# pj13.net
KiCad netlist of a schematic drawn in EAGLE
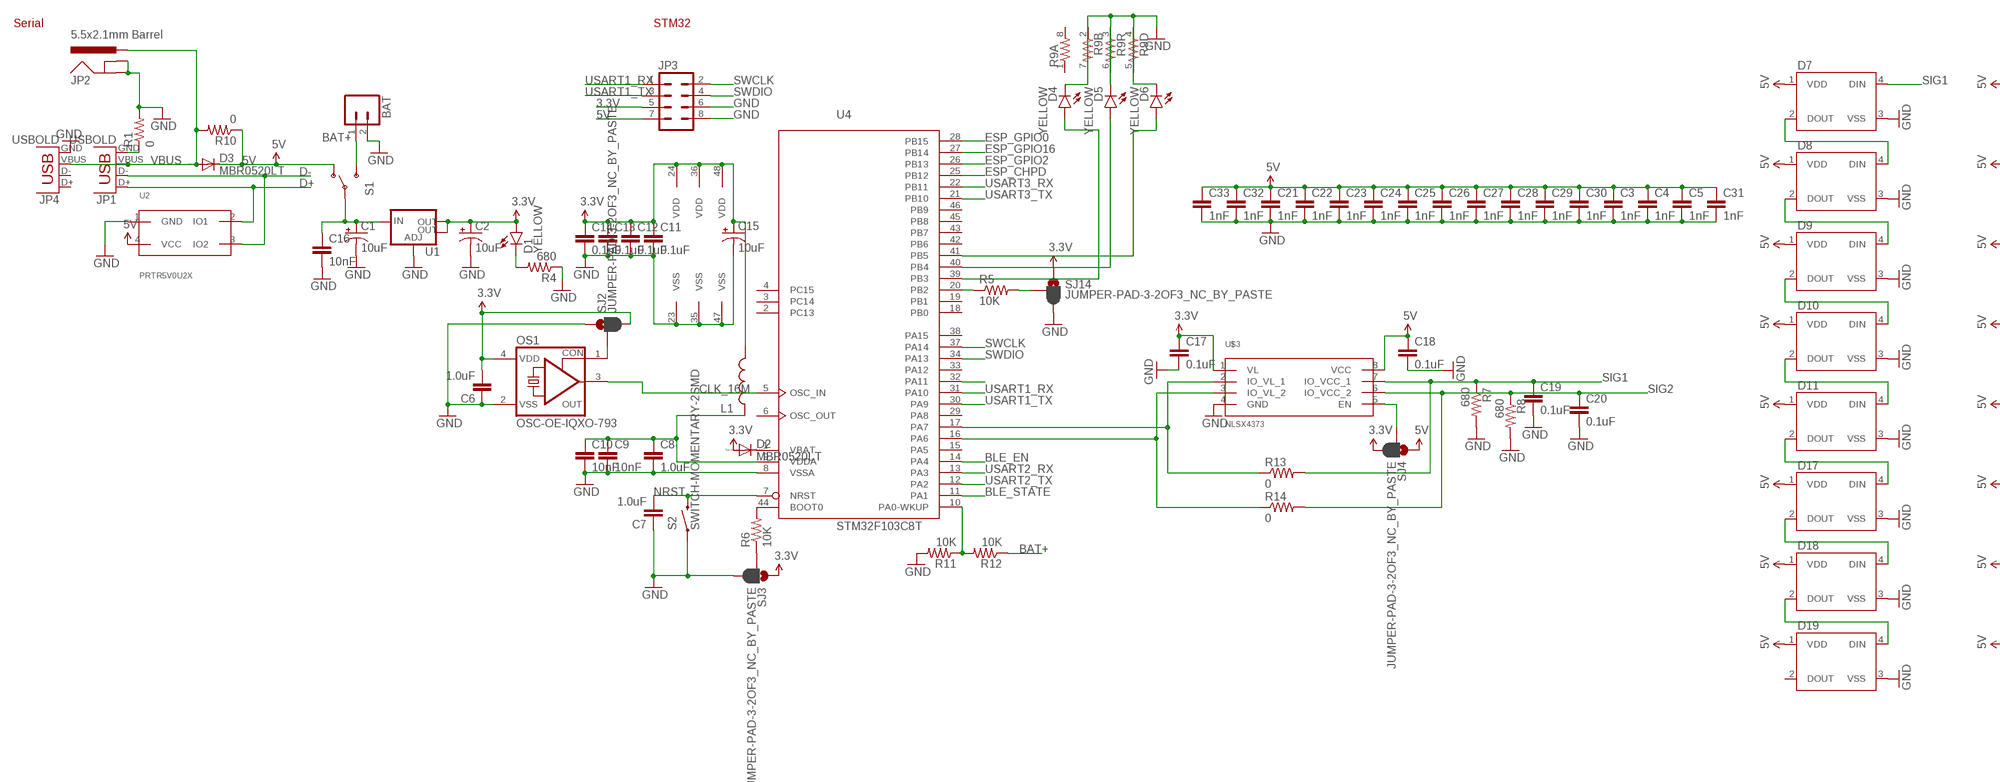
[diagram p0: schematic, sheet 1, part 1 of 2]
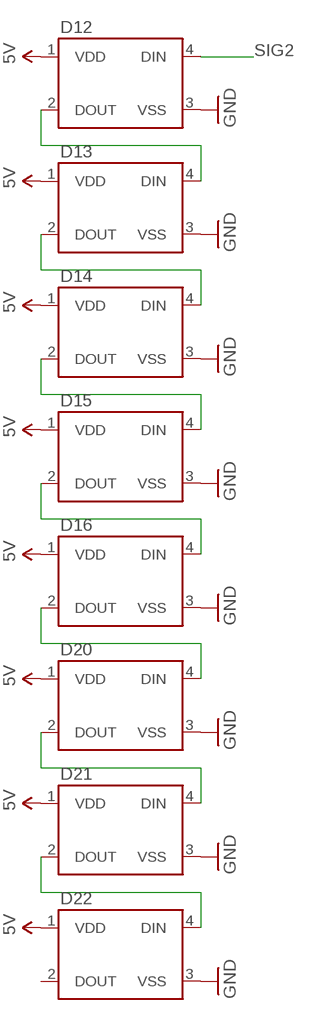
[diagram p1: schematic, sheet 1, part 2 of 2]

(export (version "E")
  (design (tool "Eeschema 10.0.6"))
  (components
    (comp (ref "BAT")
      (value "M02LOCK")
      (footprint "eagle-import:1X02_LOCK")
      (libsource (lib "eagle-import") (part "M02LOCK"))
    )
    (comp (ref "C1")
      (value "10uF")
      (footprint "eagle-import:EIA3216")
      (libsource (lib "eagle-import") (part "10UF-16V-10%(TANT)"))
    )
    (comp (ref "C2")
      (value "10uF")
      (footprint "eagle-import:EIA3216")
      (libsource (lib "eagle-import") (part "10UF-16V-10%(TANT)"))
    )
    (comp (ref "C3")
      (value "1nF")
      (footprint "eagle-import:0603-CAP")
      (libsource (lib "eagle-import") (part "0.1UF-25V-5%(0603)"))
    )
    (comp (ref "C4")
      (value "1nF")
      (footprint "eagle-import:0603-CAP")
      (libsource (lib "eagle-import") (part "0.1UF-25V-5%(0603)"))
    )
    (comp (ref "C5")
      (value "1nF")
      (footprint "eagle-import:0603-CAP")
      (libsource (lib "eagle-import") (part "0.1UF-25V-5%(0603)"))
    )
    (comp (ref "C6")
      (value "1.0uF")
      (footprint "eagle-import:0603-CAP")
      (libsource (lib "eagle-import") (part "1.0UF-16V-10%(0603)"))
    )
    (comp (ref "C7")
      (value "1.0uF")
      (footprint "eagle-import:0603-CAP")
      (libsource (lib "eagle-import") (part "1.0UF-16V-10%(0603)"))
    )
    (comp (ref "C8")
      (value "1.0uF")
      (footprint "eagle-import:0603-CAP")
      (libsource (lib "eagle-import") (part "1.0UF-16V-10%(0603)"))
    )
    (comp (ref "C9")
      (value "10nF")
      (footprint "eagle-import:0603-CAP")
      (libsource (lib "eagle-import") (part "10NF/10000PF-50V-10%(0603)"))
    )
    (comp (ref "C10")
      (value "10nF")
      (footprint "eagle-import:0603-CAP")
      (libsource (lib "eagle-import") (part "10NF/10000PF-50V-10%(0603)"))
    )
    (comp (ref "C11")
      (value "0.1uF")
      (footprint "eagle-import:0603-CAP")
      (libsource (lib "eagle-import") (part "0.1UF-25V-5%(0603)"))
    )
    (comp (ref "C12")
      (value "0.1uF")
      (footprint "eagle-import:0603-CAP")
      (libsource (lib "eagle-import") (part "0.1UF-25V-5%(0603)"))
    )
    (comp (ref "C13")
      (value "0.1uF")
      (footprint "eagle-import:0603-CAP")
      (libsource (lib "eagle-import") (part "0.1UF-25V-5%(0603)"))
    )
    (comp (ref "C14")
      (value "0.1uF")
      (footprint "eagle-import:0603-CAP")
      (libsource (lib "eagle-import") (part "0.1UF-25V-5%(0603)"))
    )
    (comp (ref "C15")
      (value "10uF")
      (footprint "eagle-import:EIA3216")
      (libsource (lib "eagle-import") (part "10UF-16V-10%(TANT)"))
    )
    (comp (ref "C16")
      (value "10nF")
      (footprint "eagle-import:0603-CAP")
      (libsource (lib "eagle-import") (part "10NF/10000PF-50V-10%(0603)"))
    )
    (comp (ref "C17")
      (value "0.1uF")
      (footprint "eagle-import:0603-CAP")
      (libsource (lib "eagle-import") (part "0.1UF-25V-5%(0603)"))
    )
    (comp (ref "C18")
      (value "0.1uF")
      (footprint "eagle-import:0603-CAP")
      (libsource (lib "eagle-import") (part "0.1UF-25V-5%(0603)"))
    )
    (comp (ref "C19")
      (value "0.1uF")
      (footprint "eagle-import:0603-CAP")
      (libsource (lib "eagle-import") (part "0.1UF-25V-5%(0603)"))
    )
    (comp (ref "C20")
      (value "0.1uF")
      (footprint "eagle-import:0603-CAP")
      (libsource (lib "eagle-import") (part "0.1UF-25V-5%(0603)"))
    )
    (comp (ref "C21")
      (value "1nF")
      (footprint "eagle-import:0603-CAP")
      (libsource (lib "eagle-import") (part "0.1UF-25V-5%(0603)"))
    )
    (comp (ref "C22")
      (value "1nF")
      (footprint "eagle-import:0603-CAP")
      (libsource (lib "eagle-import") (part "0.1UF-25V-5%(0603)"))
    )
    (comp (ref "C23")
      (value "1nF")
      (footprint "eagle-import:0603-CAP")
      (libsource (lib "eagle-import") (part "0.1UF-25V-5%(0603)"))
    )
    (comp (ref "C24")
      (value "1nF")
      (footprint "eagle-import:0603-CAP")
      (libsource (lib "eagle-import") (part "0.1UF-25V-5%(0603)"))
    )
    (comp (ref "C25")
      (value "1nF")
      (footprint "eagle-import:0603-CAP")
      (libsource (lib "eagle-import") (part "0.1UF-25V-5%(0603)"))
    )
    (comp (ref "C26")
      (value "1nF")
      (footprint "eagle-import:0603-CAP")
      (libsource (lib "eagle-import") (part "0.1UF-25V-5%(0603)"))
    )
    (comp (ref "C27")
      (value "1nF")
      (footprint "eagle-import:0603-CAP")
      (libsource (lib "eagle-import") (part "0.1UF-25V-5%(0603)"))
    )
    (comp (ref "C28")
      (value "1nF")
      (footprint "eagle-import:0603-CAP")
      (libsource (lib "eagle-import") (part "0.1UF-25V-5%(0603)"))
    )
    (comp (ref "C29")
      (value "1nF")
      (footprint "eagle-import:0603-CAP")
      (libsource (lib "eagle-import") (part "0.1UF-25V-5%(0603)"))
    )
    (comp (ref "C30")
      (value "1nF")
      (footprint "eagle-import:0603-CAP")
      (libsource (lib "eagle-import") (part "0.1UF-25V-5%(0603)"))
    )
    (comp (ref "C31")
      (value "1nF")
      (footprint "eagle-import:0603-CAP")
      (libsource (lib "eagle-import") (part "0.1UF-25V-5%(0603)"))
    )
    (comp (ref "C32")
      (value "1nF")
      (footprint "eagle-import:0603-CAP")
      (libsource (lib "eagle-import") (part "0.1UF-25V-5%(0603)"))
    )
    (comp (ref "C33")
      (value "1nF")
      (footprint "eagle-import:0603-CAP")
      (libsource (lib "eagle-import") (part "0.1UF-25V-5%(0603)"))
    )
    (comp (ref "D1")
      (value "YELLOW")
      (footprint "eagle-import:LED-1206")
      (libsource (lib "eagle-import") (part "LED-YELLOW1206"))
    )
    (comp (ref "D2")
      (value "MBR0520LT")
      (footprint "eagle-import:SOD123")
      (libsource (lib "eagle-import") (part "MBR0520LT"))
    )
    (comp (ref "D3")
      (value "MBR0520LT")
      (footprint "eagle-import:SOD123")
      (libsource (lib "eagle-import") (part "MBR0520LT"))
    )
    (comp (ref "D4")
      (value "YELLOW")
      (footprint "eagle-import:LED-1206")
      (libsource (lib "eagle-import") (part "LED-YELLOW1206"))
    )
    (comp (ref "D5")
      (value "YELLOW")
      (footprint "eagle-import:LED-1206")
      (libsource (lib "eagle-import") (part "LED-YELLOW1206"))
    )
    (comp (ref "D6")
      (value "YELLOW")
      (footprint "eagle-import:LED-1206")
      (libsource (lib "eagle-import") (part "LED-YELLOW1206"))
    )
    (comp (ref "D7")
      (value "WS2812B")
      (footprint "eagle-import:WS2812B")
      (libsource (lib "eagle-import") (part "WS2812B"))
    )
    (comp (ref "D8")
      (value "WS2812B")
      (footprint "eagle-import:WS2812B")
      (libsource (lib "eagle-import") (part "WS2812B"))
    )
    (comp (ref "D9")
      (value "WS2812B")
      (footprint "eagle-import:WS2812B")
      (libsource (lib "eagle-import") (part "WS2812B"))
    )
    (comp (ref "D10")
      (value "WS2812B")
      (footprint "eagle-import:WS2812B")
      (libsource (lib "eagle-import") (part "WS2812B"))
    )
    (comp (ref "D11")
      (value "WS2812B")
      (footprint "eagle-import:WS2812B")
      (libsource (lib "eagle-import") (part "WS2812B"))
    )
    (comp (ref "D12")
      (value "WS2812B")
      (footprint "eagle-import:WS2812B")
      (libsource (lib "eagle-import") (part "WS2812B"))
    )
    (comp (ref "D13")
      (value "WS2812B")
      (footprint "eagle-import:WS2812B")
      (libsource (lib "eagle-import") (part "WS2812B"))
    )
    (comp (ref "D14")
      (value "WS2812B")
      (footprint "eagle-import:WS2812B")
      (libsource (lib "eagle-import") (part "WS2812B"))
    )
    (comp (ref "D15")
      (value "WS2812B")
      (footprint "eagle-import:WS2812B")
      (libsource (lib "eagle-import") (part "WS2812B"))
    )
    (comp (ref "D16")
      (value "WS2812B")
      (footprint "eagle-import:WS2812B")
      (libsource (lib "eagle-import") (part "WS2812B"))
    )
    (comp (ref "D17")
      (value "WS2812B")
      (footprint "eagle-import:WS2812B")
      (libsource (lib "eagle-import") (part "WS2812B"))
    )
    (comp (ref "D18")
      (value "WS2812B")
      (footprint "eagle-import:WS2812B")
      (libsource (lib "eagle-import") (part "WS2812B"))
    )
    (comp (ref "D19")
      (value "WS2812B")
      (footprint "eagle-import:WS2812B")
      (libsource (lib "eagle-import") (part "WS2812B"))
    )
    (comp (ref "D20")
      (value "WS2812B")
      (footprint "eagle-import:WS2812B")
      (libsource (lib "eagle-import") (part "WS2812B"))
    )
    (comp (ref "D21")
      (value "WS2812B")
      (footprint "eagle-import:WS2812B")
      (libsource (lib "eagle-import") (part "WS2812B"))
    )
    (comp (ref "D22")
      (value "WS2812B")
      (footprint "eagle-import:WS2812B")
      (libsource (lib "eagle-import") (part "WS2812B"))
    )
    (comp (ref "JP1")
      (value "USBOLD")
      (footprint "eagle-import:USB-MINIB-OLD")
      (libsource (lib "eagle-import") (part "USBOLD"))
    )
    (comp (ref "JP2")
      (value "5.5x2.1mm Barrel")
      (footprint "eagle-import:POWER_JACK_SMD")
      (libsource (lib "eagle-import") (part "POWER_JACKSMD"))
    )
    (comp (ref "JP3")
      (value "M04X2SMD")
      (footprint "eagle-import:2X4_SMD")
      (libsource (lib "eagle-import") (part "M04X2SMD"))
    )
    (comp (ref "JP4")
      (value "USBOLD")
      (footprint "eagle-import:USB-MINIB-OLD")
      (libsource (lib "eagle-import") (part "USBOLD"))
    )
    (comp (ref "L1")
      (value "INDUCTOR0603")
      (footprint "eagle-import:0603")
      (libsource (lib "eagle-import") (part "INDUCTOR0603"))
    )
    (comp (ref "OS1")
      (value "OSC-OE-IQXO-793")
      (footprint "eagle-import:2.5X2-4-PAD")
      (libsource (lib "eagle-import") (part "OSC-OE-IQXO-793"))
    )
    (comp (ref "R1")
      (value "0")
      (footprint "eagle-import:0603")
      (libsource (lib "eagle-import") (part "0OHM-1/10W-5%(0603)"))
    )
    (comp (ref "R4")
      (value "680")
      (footprint "eagle-import:0603-RES")
      (libsource (lib "eagle-import") (part "680OHM1/10W5%(0603)"))
    )
    (comp (ref "R5")
      (value "10K")
      (footprint "eagle-import:0603-RES")
      (libsource (lib "eagle-import") (part "10KOHM-1/10W-1%(0603)0603"))
    )
    (comp (ref "R6")
      (value "10K")
      (footprint "eagle-import:0603-RES")
      (libsource (lib "eagle-import") (part "10KOHM-1/10W-1%(0603)0603"))
    )
    (comp (ref "R7")
      (value "680")
      (footprint "eagle-import:0603-RES")
      (libsource (lib "eagle-import") (part "680OHM1/10W5%(0603)"))
    )
    (comp (ref "R8")
      (value "680")
      (footprint "eagle-import:0603-RES")
      (libsource (lib "eagle-import") (part "680OHM1/10W5%(0603)"))
    )
    (comp (ref "R9")
      (value "RESISTOR-ARRAY0603-ARV")
      (footprint "eagle-import:0603-ARV")
      (libsource (lib "eagle-import") (part "RESISTOR-ARRAY0603-ARV"))
    )
    (comp (ref "R10")
      (value "0")
      (footprint "eagle-import:0603")
      (libsource (lib "eagle-import") (part "0OHM-1/10W-5%(0603)"))
    )
    (comp (ref "R11")
      (value "10K")
      (footprint "eagle-import:0603-RES")
      (libsource (lib "eagle-import") (part "10KOHM-1/10W-1%(0603)0603"))
    )
    (comp (ref "R12")
      (value "10K")
      (footprint "eagle-import:0603-RES")
      (libsource (lib "eagle-import") (part "10KOHM-1/10W-1%(0603)0603"))
    )
    (comp (ref "R13")
      (value "0")
      (footprint "eagle-import:0603-RES")
      (libsource (lib "eagle-import") (part "680OHM1/10W5%(0603)"))
    )
    (comp (ref "R14")
      (value "0")
      (footprint "eagle-import:0603-RES")
      (libsource (lib "eagle-import") (part "680OHM1/10W5%(0603)"))
    )
    (comp (ref "S1")
      (value "SWITCH-SPDTSMD")
      (footprint "eagle-import:AYZ0202")
      (libsource (lib "eagle-import") (part "SWITCH-SPDTSMD"))
    )
    (comp (ref "S2")
      (value "SWITCH-MOMENTARY-2SMD")
      (footprint "eagle-import:TACTILE-SWITCH-SMD")
      (libsource (lib "eagle-import") (part "SWITCH-MOMENTARY-2SMD"))
    )
    (comp (ref "SJ2")
      (value "JUMPER-PAD-3-2OF3_NC_BY_PASTE")
      (footprint "eagle-import:PAD-JUMPER-3-2OF3_NC_BY_PASTE_YES_SILK_FULL_BOX")
      (libsource (lib "eagle-import") (part "JUMPER-PAD-3-2OF3_NC_BY_PASTE"))
    )
    (comp (ref "SJ3")
      (value "JUMPER-PAD-3-2OF3_NC_BY_PASTE")
      (footprint "eagle-import:PAD-JUMPER-3-2OF3_NC_BY_PASTE_YES_SILK_FULL_BOX")
      (libsource (lib "eagle-import") (part "JUMPER-PAD-3-2OF3_NC_BY_PASTE"))
    )
    (comp (ref "SJ4")
      (value "JUMPER-PAD-3-2OF3_NC_BY_PASTE")
      (footprint "eagle-import:PAD-JUMPER-3-2OF3_NC_BY_PASTE_YES_SILK_FULL_BOX")
      (libsource (lib "eagle-import") (part "JUMPER-PAD-3-2OF3_NC_BY_PASTE"))
    )
    (comp (ref "SJ14")
      (value "JUMPER-PAD-3-2OF3_NC_BY_PASTE")
      (footprint "eagle-import:PAD-JUMPER-3-2OF3_NC_BY_PASTE_YES_SILK_FULL_BOX")
      (libsource (lib "eagle-import") (part "JUMPER-PAD-3-2OF3_NC_BY_PASTE"))
    )
    (comp (ref "U$3")
      (value "NLSX4373")
      (footprint "eagle-import:SO08")
      (libsource (lib "eagle-import") (part "NLSX4373"))
    )
    (comp (ref "U1")
      (value "V_REG_LM1117SOT223")
      (footprint "eagle-import:SOT223")
      (libsource (lib "eagle-import") (part "V_REG_LM1117SOT223"))
    )
    (comp (ref "U2")
      (value "PRTR5V0U2X")
      (footprint "eagle-import:SOT143")
      (libsource (lib "eagle-import") (part "PRTR5V0U2X"))
    )
    (comp (ref "U4")
      (value "STM32F103C8T")
      (footprint "eagle-import:LQFP48")
      (libsource (lib "eagle-import") (part "STM32F103CT8"))
    )
  )
  (nets
    (net (code "1") (name "/BAT+") (class "Default")
      (node (ref "BAT") (pin "1") (pinfunction "1_1") (pintype "passive"))
      (node (ref "R12") (pin "1") (pinfunction "1_1") (pintype "passive"))
      (node (ref "S1") (pin "3") (pinfunction "S_3") (pintype "passive"))
    )
    (net (code "2") (name "/BLE_EN") (class "Default")
      (node (ref "U4") (pin "14") (pinfunction "PA4_14") (pintype "bidirectional"))
    )
    (net (code "3") (name "/BLE_STATE") (class "Default")
      (node (ref "U4") (pin "11") (pinfunction "PA1_11") (pintype "bidirectional"))
    )
    (net (code "4") (name "/CLK_16M") (class "Default")
      (node (ref "OS1") (pin "3") (pinfunction "OUT_3") (pintype "output"))
      (node (ref "U4") (pin "5") (pinfunction "OSC_IN_5") (pintype "bidirectional"))
    )
    (net (code "5") (name "/D+") (class "Default")
      (node (ref "JP1") (pin "D+") (pinfunction "D+_D+") (pintype "bidirectional"))
      (node (ref "U2") (pin "2") (pinfunction "IO1_2") (pintype "bidirectional"))
    )
    (net (code "6") (name "/D-") (class "Default")
      (node (ref "JP1") (pin "D-") (pinfunction "D-_D-") (pintype "bidirectional"))
      (node (ref "U2") (pin "3") (pinfunction "IO2_3") (pintype "bidirectional"))
    )
    (net (code "7") (name "/ESP_CHPD") (class "Default")
      (node (ref "U4") (pin "25") (pinfunction "PB12_25") (pintype "bidirectional"))
    )
    (net (code "8") (name "/ESP_GPIO0") (class "Default")
      (node (ref "U4") (pin "28") (pinfunction "PB15_28") (pintype "bidirectional"))
    )
    (net (code "9") (name "/ESP_GPIO2") (class "Default")
      (node (ref "U4") (pin "26") (pinfunction "PB13_26") (pintype "bidirectional"))
    )
    (net (code "10") (name "/ESP_GPIO16") (class "Default")
      (node (ref "U4") (pin "27") (pinfunction "PB14_27") (pintype "bidirectional"))
    )
    (net (code "11") (name "/NRST") (class "Default")
      (node (ref "C7") (pin "2") (pinfunction "2_2") (pintype "passive"))
      (node (ref "S2") (pin "3") (pinfunction "2_3") (pintype "passive"))
      (node (ref "U4") (pin "7") (pinfunction "NRST_7") (pintype "bidirectional"))
    )
    (net (code "12") (name "/SIG1") (class "Default")
      (node (ref "C19") (pin "1") (pinfunction "1_1") (pintype "passive"))
      (node (ref "D7") (pin "4") (pinfunction "DIN_4") (pintype "input"))
      (node (ref "R13") (pin "2") (pinfunction "2_2") (pintype "passive"))
      (node (ref "R7") (pin "1") (pinfunction "1_1") (pintype "passive"))
      (node (ref "U$3") (pin "7") (pinfunction "IO_VCC_1_7") (pintype "bidirectional"))
    )
    (net (code "13") (name "/SIG2") (class "Default")
      (node (ref "C20") (pin "1") (pinfunction "1_1") (pintype "passive"))
      (node (ref "D12") (pin "4") (pinfunction "DIN_4") (pintype "input"))
      (node (ref "R14") (pin "2") (pinfunction "2_2") (pintype "passive"))
      (node (ref "R8") (pin "1") (pinfunction "1_1") (pintype "passive"))
      (node (ref "U$3") (pin "6") (pinfunction "IO_VCC_2_6") (pintype "bidirectional"))
    )
    (net (code "14") (name "/SWCLK") (class "Default")
      (node (ref "JP3") (pin "2") (pinfunction "2_2") (pintype "passive"))
      (node (ref "U4") (pin "37") (pinfunction "PA14_37") (pintype "bidirectional"))
    )
    (net (code "15") (name "/SWDIO") (class "Default")
      (node (ref "JP3") (pin "4") (pinfunction "4_4") (pintype "passive"))
      (node (ref "U4") (pin "34") (pinfunction "PA13_34") (pintype "bidirectional"))
    )
    (net (code "16") (name "/USART1_RX") (class "Default")
      (node (ref "JP3") (pin "1") (pinfunction "1_1") (pintype "passive"))
      (node (ref "U4") (pin "31") (pinfunction "PA10_31") (pintype "bidirectional"))
    )
    (net (code "17") (name "/USART1_TX") (class "Default")
      (node (ref "JP3") (pin "3") (pinfunction "3_3") (pintype "passive"))
      (node (ref "U4") (pin "30") (pinfunction "PA9_30") (pintype "bidirectional"))
    )
    (net (code "18") (name "/USART2_RX") (class "Default")
      (node (ref "U4") (pin "13") (pinfunction "PA3_13") (pintype "bidirectional"))
    )
    (net (code "19") (name "/USART2_TX") (class "Default")
      (node (ref "U4") (pin "12") (pinfunction "PA2_12") (pintype "bidirectional"))
    )
    (net (code "20") (name "/USART3_RX") (class "Default")
      (node (ref "U4") (pin "22") (pinfunction "PB11_22") (pintype "bidirectional"))
    )
    (net (code "21") (name "/USART3_TX") (class "Default")
      (node (ref "U4") (pin "21") (pinfunction "PB10_21") (pintype "bidirectional"))
    )
    (net (code "22") (name "/VBUS") (class "Default")
      (node (ref "D3") (pin "A") (pinfunction "A_A") (pintype "passive"))
      (node (ref "JP1") (pin "VBUS") (pinfunction "VBUS_VBUS") (pintype "bidirectional"))
      (node (ref "JP2") (pin "VIN0") (pinfunction "PWR_VIN0") (pintype "bidirectional"))
      (node (ref "JP4") (pin "VBUS") (pinfunction "VBUS_VBUS") (pintype "bidirectional"))
      (node (ref "R10") (pin "2") (pinfunction "2_2") (pintype "passive"))
    )
    (net (code "23") (name "3.3V") (class "Default")
      (node (ref "C11") (pin "1") (pinfunction "1_1") (pintype "passive"))
      (node (ref "C12") (pin "1") (pinfunction "1_1") (pintype "passive"))
      (node (ref "C13") (pin "1") (pinfunction "1_1") (pintype "passive"))
      (node (ref "C14") (pin "1") (pinfunction "1_1") (pintype "passive"))
      (node (ref "C15") (pin "A") (pinfunction "+_A") (pintype "passive"))
      (node (ref "C17") (pin "1") (pinfunction "1_1") (pintype "passive"))
      (node (ref "C2") (pin "A") (pinfunction "+_A") (pintype "passive"))
      (node (ref "C6") (pin "2") (pinfunction "2_2") (pintype "passive"))
      (node (ref "D1") (pin "A") (pinfunction "A_A") (pintype "passive"))
      (node (ref "D2") (pin "A") (pinfunction "A_A") (pintype "passive"))
      (node (ref "JP3") (pin "5") (pinfunction "5_5") (pintype "passive"))
      (node (ref "L1") (pin "2") (pinfunction "2_2") (pintype "passive"))
      (node (ref "OS1") (pin "4") (pinfunction "VDD_4") (pintype "power_in"))
      (node (ref "SJ14") (pin "1") (pinfunction "1_1") (pintype "passive"))
      (node (ref "SJ2") (pin "3") (pinfunction "3_3") (pintype "passive"))
      (node (ref "SJ3") (pin "1") (pinfunction "1_1") (pintype "passive"))
      (node (ref "SJ4") (pin "3") (pinfunction "3_3") (pintype "passive"))
      (node (ref "U$3") (pin "1") (pinfunction "VL_1") (pintype "bidirectional"))
      (node (ref "U1") (pin "2") (pinfunction "OUT_2") (pintype "output"))
      (node (ref "U1") (pin "4") (pinfunction "OUT_4") (pintype "output"))
      (node (ref "U4") (pin "24") (pinfunction "VDD_24") (pintype "power_in"))
      (node (ref "U4") (pin "36") (pinfunction "VDD_36") (pintype "power_in"))
      (node (ref "U4") (pin "48") (pinfunction "VDD_48") (pintype "power_in"))
    )
    (net (code "24") (name "5V") (class "Default")
      (node (ref "C18") (pin "1") (pinfunction "1_1") (pintype "passive"))
      (node (ref "C21") (pin "1") (pinfunction "1_1") (pintype "passive"))
      (node (ref "C22") (pin "1") (pinfunction "1_1") (pintype "passive"))
      (node (ref "C23") (pin "1") (pinfunction "1_1") (pintype "passive"))
      (node (ref "C24") (pin "1") (pinfunction "1_1") (pintype "passive"))
      (node (ref "C25") (pin "1") (pinfunction "1_1") (pintype "passive"))
      (node (ref "C26") (pin "1") (pinfunction "1_1") (pintype "passive"))
      (node (ref "C27") (pin "1") (pinfunction "1_1") (pintype "passive"))
      (node (ref "C28") (pin "1") (pinfunction "1_1") (pintype "passive"))
      (node (ref "C29") (pin "1") (pinfunction "1_1") (pintype "passive"))
      (node (ref "C3") (pin "1") (pinfunction "1_1") (pintype "passive"))
      (node (ref "C30") (pin "1") (pinfunction "1_1") (pintype "passive"))
      (node (ref "C31") (pin "1") (pinfunction "1_1") (pintype "passive"))
      (node (ref "C32") (pin "1") (pinfunction "1_1") (pintype "passive"))
      (node (ref "C33") (pin "1") (pinfunction "1_1") (pintype "passive"))
      (node (ref "C4") (pin "1") (pinfunction "1_1") (pintype "passive"))
      (node (ref "C5") (pin "1") (pinfunction "1_1") (pintype "passive"))
      (node (ref "D10") (pin "1") (pinfunction "VDD_1") (pintype "power_in"))
      (node (ref "D11") (pin "1") (pinfunction "VDD_1") (pintype "power_in"))
      (node (ref "D12") (pin "1") (pinfunction "VDD_1") (pintype "power_in"))
      (node (ref "D13") (pin "1") (pinfunction "VDD_1") (pintype "power_in"))
      (node (ref "D14") (pin "1") (pinfunction "VDD_1") (pintype "power_in"))
      (node (ref "D15") (pin "1") (pinfunction "VDD_1") (pintype "power_in"))
      (node (ref "D16") (pin "1") (pinfunction "VDD_1") (pintype "power_in"))
      (node (ref "D17") (pin "1") (pinfunction "VDD_1") (pintype "power_in"))
      (node (ref "D18") (pin "1") (pinfunction "VDD_1") (pintype "power_in"))
      (node (ref "D19") (pin "1") (pinfunction "VDD_1") (pintype "power_in"))
      (node (ref "D20") (pin "1") (pinfunction "VDD_1") (pintype "power_in"))
      (node (ref "D21") (pin "1") (pinfunction "VDD_1") (pintype "power_in"))
      (node (ref "D22") (pin "1") (pinfunction "VDD_1") (pintype "power_in"))
      (node (ref "D3") (pin "C") (pinfunction "C_C") (pintype "passive"))
      (node (ref "D7") (pin "1") (pinfunction "VDD_1") (pintype "power_in"))
      (node (ref "D8") (pin "1") (pinfunction "VDD_1") (pintype "power_in"))
      (node (ref "D9") (pin "1") (pinfunction "VDD_1") (pintype "power_in"))
      (node (ref "JP3") (pin "7") (pinfunction "7_7") (pintype "passive"))
      (node (ref "R10") (pin "1") (pinfunction "1_1") (pintype "passive"))
      (node (ref "S1") (pin "1") (pinfunction "O_1") (pintype "passive"))
      (node (ref "SJ4") (pin "1") (pinfunction "1_1") (pintype "passive"))
      (node (ref "U$3") (pin "8") (pinfunction "VCC_8") (pintype "bidirectional"))
      (node (ref "U2") (pin "4") (pinfunction "VCC_4") (pintype "bidirectional"))
    )
    (net (code "25") (name "GND") (class "Default")
      (node (ref "BAT") (pin "2") (pinfunction "2_2") (pintype "passive"))
      (node (ref "C1") (pin "C") (pinfunction "-_C") (pintype "passive"))
      (node (ref "C10") (pin "2") (pinfunction "2_2") (pintype "passive"))
      (node (ref "C11") (pin "2") (pinfunction "2_2") (pintype "passive"))
      (node (ref "C12") (pin "2") (pinfunction "2_2") (pintype "passive"))
      (node (ref "C13") (pin "2") (pinfunction "2_2") (pintype "passive"))
      (node (ref "C14") (pin "2") (pinfunction "2_2") (pintype "passive"))
      (node (ref "C15") (pin "C") (pinfunction "-_C") (pintype "passive"))
      (node (ref "C16") (pin "2") (pinfunction "2_2") (pintype "passive"))
      (node (ref "C17") (pin "2") (pinfunction "2_2") (pintype "passive"))
      (node (ref "C18") (pin "2") (pinfunction "2_2") (pintype "passive"))
      (node (ref "C19") (pin "2") (pinfunction "2_2") (pintype "passive"))
      (node (ref "C2") (pin "C") (pinfunction "-_C") (pintype "passive"))
      (node (ref "C20") (pin "2") (pinfunction "2_2") (pintype "passive"))
      (node (ref "C21") (pin "2") (pinfunction "2_2") (pintype "passive"))
      (node (ref "C22") (pin "2") (pinfunction "2_2") (pintype "passive"))
      (node (ref "C23") (pin "2") (pinfunction "2_2") (pintype "passive"))
      (node (ref "C24") (pin "2") (pinfunction "2_2") (pintype "passive"))
      (node (ref "C25") (pin "2") (pinfunction "2_2") (pintype "passive"))
      (node (ref "C26") (pin "2") (pinfunction "2_2") (pintype "passive"))
      (node (ref "C27") (pin "2") (pinfunction "2_2") (pintype "passive"))
      (node (ref "C28") (pin "2") (pinfunction "2_2") (pintype "passive"))
      (node (ref "C29") (pin "2") (pinfunction "2_2") (pintype "passive"))
      (node (ref "C3") (pin "2") (pinfunction "2_2") (pintype "passive"))
      (node (ref "C30") (pin "2") (pinfunction "2_2") (pintype "passive"))
      (node (ref "C31") (pin "2") (pinfunction "2_2") (pintype "passive"))
      (node (ref "C32") (pin "2") (pinfunction "2_2") (pintype "passive"))
      (node (ref "C33") (pin "2") (pinfunction "2_2") (pintype "passive"))
      (node (ref "C4") (pin "2") (pinfunction "2_2") (pintype "passive"))
      (node (ref "C5") (pin "2") (pinfunction "2_2") (pintype "passive"))
      (node (ref "C6") (pin "1") (pinfunction "1_1") (pintype "passive"))
      (node (ref "C7") (pin "1") (pinfunction "1_1") (pintype "passive"))
      (node (ref "C8") (pin "2") (pinfunction "2_2") (pintype "passive"))
      (node (ref "C9") (pin "2") (pinfunction "2_2") (pintype "passive"))
      (node (ref "D10") (pin "3") (pinfunction "VSS_3") (pintype "power_in"))
      (node (ref "D11") (pin "3") (pinfunction "VSS_3") (pintype "power_in"))
      (node (ref "D12") (pin "3") (pinfunction "VSS_3") (pintype "power_in"))
      (node (ref "D13") (pin "3") (pinfunction "VSS_3") (pintype "power_in"))
      (node (ref "D14") (pin "3") (pinfunction "VSS_3") (pintype "power_in"))
      (node (ref "D15") (pin "3") (pinfunction "VSS_3") (pintype "power_in"))
      (node (ref "D16") (pin "3") (pinfunction "VSS_3") (pintype "power_in"))
      (node (ref "D17") (pin "3") (pinfunction "VSS_3") (pintype "power_in"))
      (node (ref "D18") (pin "3") (pinfunction "VSS_3") (pintype "power_in"))
      (node (ref "D19") (pin "3") (pinfunction "VSS_3") (pintype "power_in"))
      (node (ref "D20") (pin "3") (pinfunction "VSS_3") (pintype "power_in"))
      (node (ref "D21") (pin "3") (pinfunction "VSS_3") (pintype "power_in"))
      (node (ref "D22") (pin "3") (pinfunction "VSS_3") (pintype "power_in"))
      (node (ref "D7") (pin "3") (pinfunction "VSS_3") (pintype "power_in"))
      (node (ref "D8") (pin "3") (pinfunction "VSS_3") (pintype "power_in"))
      (node (ref "D9") (pin "3") (pinfunction "VSS_3") (pintype "power_in"))
      (node (ref "JP2") (pin "GND") (pinfunction "GNDBREAK_GND") (pintype "bidirectional"))
      (node (ref "JP2") (pin "P$4") (pinfunction "GND_P$4") (pintype "bidirectional"))
      (node (ref "JP3") (pin "6") (pinfunction "6_6") (pintype "passive"))
      (node (ref "JP3") (pin "8") (pinfunction "8_8") (pintype "passive"))
      (node (ref "JP4") (pin "GND") (pinfunction "GND_GND") (pintype "bidirectional"))
      (node (ref "OS1") (pin "2") (pinfunction "VSS_2") (pintype "power_in"))
      (node (ref "R1") (pin "2") (pinfunction "2_2") (pintype "passive"))
      (node (ref "R11") (pin "2") (pinfunction "2_2") (pintype "passive"))
      (node (ref "R4") (pin "1") (pinfunction "1_1") (pintype "passive"))
      (node (ref "R7") (pin "2") (pinfunction "2_2") (pintype "passive"))
      (node (ref "R8") (pin "2") (pinfunction "2_2") (pintype "passive"))
      (node (ref "R9") (pin "5") (pinfunction "2_5") (pintype "passive"))
      (node (ref "R9") (pin "6") (pinfunction "2_6") (pintype "passive"))
      (node (ref "R9") (pin "7") (pinfunction "2_7") (pintype "passive"))
      (node (ref "S2") (pin "1") (pinfunction "1_1") (pintype "passive"))
      (node (ref "SJ14") (pin "3") (pinfunction "3_3") (pintype "passive"))
      (node (ref "SJ2") (pin "1") (pinfunction "1_1") (pintype "passive"))
      (node (ref "SJ3") (pin "3") (pinfunction "3_3") (pintype "passive"))
      (node (ref "U$3") (pin "4") (pinfunction "GND_4") (pintype "bidirectional"))
      (node (ref "U1") (pin "1") (pinfunction "ADJ_1") (pintype "input"))
      (node (ref "U2") (pin "1") (pinfunction "GND_1") (pintype "bidirectional"))
      (node (ref "U4") (pin "23") (pinfunction "VSS_23") (pintype "power_in"))
      (node (ref "U4") (pin "35") (pinfunction "VSS_35") (pintype "power_in"))
      (node (ref "U4") (pin "47") (pinfunction "VSS_47") (pintype "power_in"))
      (node (ref "U4") (pin "8") (pinfunction "VSSA_8") (pintype "power_in"))
    )
    (net (code "26") (name "Net-(C1-+)") (class "Default")
      (node (ref "C1") (pin "A") (pinfunction "+_A") (pintype "passive"))
      (node (ref "C16") (pin "1") (pinfunction "1_1") (pintype "passive"))
      (node (ref "S1") (pin "2") (pinfunction "P_2") (pintype "passive"))
      (node (ref "U1") (pin "3") (pinfunction "IN_3") (pintype "input"))
    )
    (net (code "27") (name "Net-(D1-PadC)") (class "Default")
      (node (ref "D1") (pin "C") (pinfunction "C_C") (pintype "passive"))
      (node (ref "R4") (pin "2") (pinfunction "2_2") (pintype "passive"))
    )
    (net (code "28") (name "Net-(D7-DOUT)") (class "Default")
      (node (ref "D7") (pin "2") (pinfunction "DOUT_2") (pintype "output"))
      (node (ref "D8") (pin "4") (pinfunction "DIN_4") (pintype "input"))
    )
    (net (code "29") (name "Net-(D8-DOUT)") (class "Default")
      (node (ref "D8") (pin "2") (pinfunction "DOUT_2") (pintype "output"))
      (node (ref "D9") (pin "4") (pinfunction "DIN_4") (pintype "input"))
    )
    (net (code "30") (name "Net-(D10-DIN)") (class "Default")
      (node (ref "D10") (pin "4") (pinfunction "DIN_4") (pintype "input"))
      (node (ref "D9") (pin "2") (pinfunction "DOUT_2") (pintype "output"))
    )
    (net (code "31") (name "Net-(D10-DOUT)") (class "Default")
      (node (ref "D10") (pin "2") (pinfunction "DOUT_2") (pintype "output"))
      (node (ref "D11") (pin "4") (pinfunction "DIN_4") (pintype "input"))
    )
    (net (code "32") (name "Net-(D11-DOUT)") (class "Default")
      (node (ref "D11") (pin "2") (pinfunction "DOUT_2") (pintype "output"))
      (node (ref "D17") (pin "4") (pinfunction "DIN_4") (pintype "input"))
    )
    (net (code "33") (name "Net-(D12-DOUT)") (class "Default")
      (node (ref "D12") (pin "2") (pinfunction "DOUT_2") (pintype "output"))
      (node (ref "D13") (pin "4") (pinfunction "DIN_4") (pintype "input"))
    )
    (net (code "34") (name "Net-(D13-DOUT)") (class "Default")
      (node (ref "D13") (pin "2") (pinfunction "DOUT_2") (pintype "output"))
      (node (ref "D14") (pin "4") (pinfunction "DIN_4") (pintype "input"))
    )
    (net (code "35") (name "Net-(D14-DOUT)") (class "Default")
      (node (ref "D14") (pin "2") (pinfunction "DOUT_2") (pintype "output"))
      (node (ref "D15") (pin "4") (pinfunction "DIN_4") (pintype "input"))
    )
    (net (code "36") (name "Net-(D15-DOUT)") (class "Default")
      (node (ref "D15") (pin "2") (pinfunction "DOUT_2") (pintype "output"))
      (node (ref "D16") (pin "4") (pinfunction "DIN_4") (pintype "input"))
    )
    (net (code "37") (name "Net-(D16-DOUT)") (class "Default")
      (node (ref "D16") (pin "2") (pinfunction "DOUT_2") (pintype "output"))
      (node (ref "D20") (pin "4") (pinfunction "DIN_4") (pintype "input"))
    )
    (net (code "38") (name "Net-(D17-DOUT)") (class "Default")
      (node (ref "D17") (pin "2") (pinfunction "DOUT_2") (pintype "output"))
      (node (ref "D18") (pin "4") (pinfunction "DIN_4") (pintype "input"))
    )
    (net (code "39") (name "Net-(D18-DOUT)") (class "Default")
      (node (ref "D18") (pin "2") (pinfunction "DOUT_2") (pintype "output"))
      (node (ref "D19") (pin "4") (pinfunction "DIN_4") (pintype "input"))
    )
    (net (code "40") (name "Net-(D20-DOUT)") (class "Default")
      (node (ref "D20") (pin "2") (pinfunction "DOUT_2") (pintype "output"))
      (node (ref "D21") (pin "4") (pinfunction "DIN_4") (pintype "input"))
    )
    (net (code "41") (name "Net-(D21-DOUT)") (class "Default")
      (node (ref "D21") (pin "2") (pinfunction "DOUT_2") (pintype "output"))
      (node (ref "D22") (pin "4") (pinfunction "DIN_4") (pintype "input"))
    )
    (net (code "42") (name "Net-(JP1-PadGND)") (class "Default")
      (node (ref "JP1") (pin "GND") (pinfunction "GND_GND") (pintype "bidirectional"))
      (node (ref "R1") (pin "1") (pinfunction "1_1") (pintype "passive"))
    )
    (net (code "43") (name "Net-(OS1-CON)") (class "Default")
      (node (ref "OS1") (pin "1") (pinfunction "CON_1") (pintype "input"))
      (node (ref "SJ2") (pin "2") (pinfunction "2_2") (pintype "passive"))
    )
    (net (code "44") (name "Net-(R5-Pad2)") (class "Default")
      (node (ref "R5") (pin "2") (pinfunction "2_2") (pintype "passive"))
      (node (ref "SJ14") (pin "2") (pinfunction "2_2") (pintype "passive"))
    )
    (net (code "45") (name "Net-(R6-Pad1)") (class "Default")
      (node (ref "R6") (pin "1") (pinfunction "1_1") (pintype "passive"))
      (node (ref "SJ3") (pin "2") (pinfunction "2_2") (pintype "passive"))
    )
    (net (code "46") (name "Net-(R9B-1)") (class "Default")
      (node (ref "D4") (pin "C") (pinfunction "C_C") (pintype "passive"))
      (node (ref "R9") (pin "2") (pinfunction "1_2") (pintype "passive"))
    )
    (net (code "47") (name "Net-(R9C-1)") (class "Default")
      (node (ref "D6") (pin "C") (pinfunction "C_C") (pintype "passive"))
      (node (ref "R9") (pin "4") (pinfunction "1_4") (pintype "passive"))
    )
    (net (code "48") (name "Net-(R9D-1)") (class "Default")
      (node (ref "D5") (pin "C") (pinfunction "C_C") (pintype "passive"))
      (node (ref "R9") (pin "3") (pinfunction "1_3") (pintype "passive"))
    )
    (net (code "49") (name "Net-(U$3-EN)") (class "Default")
      (node (ref "SJ4") (pin "2") (pinfunction "2_2") (pintype "passive"))
      (node (ref "U$3") (pin "5") (pinfunction "EN_5") (pintype "bidirectional"))
    )
    (net (code "50") (name "Net-(U$3-IO_VL_1)") (class "Default")
      (node (ref "R13") (pin "1") (pinfunction "1_1") (pintype "passive"))
      (node (ref "U$3") (pin "2") (pinfunction "IO_VL_1_2") (pintype "bidirectional"))
      (node (ref "U4") (pin "17") (pinfunction "PA7_17") (pintype "bidirectional"))
    )
    (net (code "51") (name "Net-(U$3-IO_VL_2)") (class "Default")
      (node (ref "R14") (pin "1") (pinfunction "1_1") (pintype "passive"))
      (node (ref "U$3") (pin "3") (pinfunction "IO_VL_2_3") (pintype "bidirectional"))
      (node (ref "U4") (pin "16") (pinfunction "PA6_16") (pintype "bidirectional"))
    )
    (net (code "52") (name "Net-(U4A-BOOT0)") (class "Default")
      (node (ref "R6") (pin "2") (pinfunction "2_2") (pintype "passive"))
      (node (ref "U4") (pin "44") (pinfunction "BOOT0_44") (pintype "input"))
    )
    (net (code "53") (name "Net-(U4A-PA0-WKUP)") (class "Default")
      (node (ref "R11") (pin "1") (pinfunction "1_1") (pintype "passive"))
      (node (ref "R12") (pin "2") (pinfunction "2_2") (pintype "passive"))
      (node (ref "U4") (pin "10") (pinfunction "PA0-WKUP_10") (pintype "bidirectional"))
    )
    (net (code "54") (name "Net-(U4A-PB2)") (class "Default")
      (node (ref "R5") (pin "1") (pinfunction "1_1") (pintype "passive"))
      (node (ref "U4") (pin "20") (pinfunction "PB2_20") (pintype "bidirectional"))
    )
    (net (code "55") (name "Net-(U4A-PB3)") (class "Default")
      (node (ref "D4") (pin "A") (pinfunction "A_A") (pintype "passive"))
      (node (ref "U4") (pin "39") (pinfunction "PB3_39") (pintype "bidirectional"))
    )
    (net (code "56") (name "Net-(U4A-PB4)") (class "Default")
      (node (ref "D5") (pin "A") (pinfunction "A_A") (pintype "passive"))
      (node (ref "U4") (pin "40") (pinfunction "PB4_40") (pintype "bidirectional"))
    )
    (net (code "57") (name "Net-(U4A-PB5)") (class "Default")
      (node (ref "D6") (pin "A") (pinfunction "A_A") (pintype "passive"))
      (node (ref "U4") (pin "41") (pinfunction "PB5_41") (pintype "bidirectional"))
    )
    (net (code "58") (name "Net-(U4A-VBAT)") (class "Default")
      (node (ref "D2") (pin "C") (pinfunction "C_C") (pintype "passive"))
      (node (ref "U4") (pin "1") (pinfunction "VBAT_1") (pintype "power_in"))
    )
    (net (code "59") (name "Net-(U4A-VDDA)") (class "Default")
      (node (ref "C10") (pin "1") (pinfunction "1_1") (pintype "passive"))
      (node (ref "C8") (pin "1") (pinfunction "1_1") (pintype "passive"))
      (node (ref "C9") (pin "1") (pinfunction "1_1") (pintype "passive"))
      (node (ref "L1") (pin "1") (pinfunction "1_1") (pintype "passive"))
      (node (ref "U4") (pin "9") (pinfunction "VDDA_9") (pintype "power_in"))
    )
    (net (code "60") (name "unconnected-(D19-DOUT-Pad2)") (class "Default")
      (node (ref "D19") (pin "2") (pinfunction "DOUT_2") (pintype "output"))
    )
    (net (code "61") (name "unconnected-(D22-DOUT-Pad2)") (class "Default")
      (node (ref "D22") (pin "2") (pinfunction "DOUT_2") (pintype "output"))
    )
    (net (code "62") (name "unconnected-(JP4-PadD+)") (class "Default")
      (node (ref "JP4") (pin "D+") (pinfunction "D+_D+") (pintype "bidirectional"))
    )
    (net (code "63") (name "unconnected-(JP4-PadD-)") (class "Default")
      (node (ref "JP4") (pin "D-") (pinfunction "D-_D-") (pintype "bidirectional"))
    )
    (net (code "64") (name "unconnected-(R9-Pad1)") (class "Default")
      (node (ref "R9") (pin "1") (pinfunction "1_1") (pintype "passive"))
    )
    (net (code "65") (name "unconnected-(R9A-2-Pad8)") (class "Default")
      (node (ref "R9") (pin "8") (pinfunction "2_8") (pintype "passive"))
    )
    (net (code "66") (name "unconnected-(U4A-OSC_OUT-Pad6)") (class "Default")
      (node (ref "U4") (pin "6") (pinfunction "OSC_OUT_6") (pintype "bidirectional"))
    )
    (net (code "67") (name "unconnected-(U4A-PA5-Pad15)") (class "Default")
      (node (ref "U4") (pin "15") (pinfunction "PA5_15") (pintype "bidirectional"))
    )
    (net (code "68") (name "unconnected-(U4A-PA8-Pad29)") (class "Default")
      (node (ref "U4") (pin "29") (pinfunction "PA8_29") (pintype "bidirectional"))
    )
    (net (code "69") (name "unconnected-(U4A-PA11-Pad32)") (class "Default")
      (node (ref "U4") (pin "32") (pinfunction "PA11_32") (pintype "bidirectional"))
    )
    (net (code "70") (name "unconnected-(U4A-PA12-Pad33)") (class "Default")
      (node (ref "U4") (pin "33") (pinfunction "PA12_33") (pintype "bidirectional"))
    )
    (net (code "71") (name "unconnected-(U4A-PA15-Pad38)") (class "Default")
      (node (ref "U4") (pin "38") (pinfunction "PA15_38") (pintype "bidirectional"))
    )
    (net (code "72") (name "unconnected-(U4A-PB0-Pad18)") (class "Default")
      (node (ref "U4") (pin "18") (pinfunction "PB0_18") (pintype "bidirectional"))
    )
    (net (code "73") (name "unconnected-(U4A-PB1-Pad19)") (class "Default")
      (node (ref "U4") (pin "19") (pinfunction "PB1_19") (pintype "bidirectional"))
    )
    (net (code "74") (name "unconnected-(U4A-PB6-Pad42)") (class "Default")
      (node (ref "U4") (pin "42") (pinfunction "PB6_42") (pintype "bidirectional"))
    )
    (net (code "75") (name "unconnected-(U4A-PB7-Pad43)") (class "Default")
      (node (ref "U4") (pin "43") (pinfunction "PB7_43") (pintype "bidirectional"))
    )
    (net (code "76") (name "unconnected-(U4A-PB8-Pad45)") (class "Default")
      (node (ref "U4") (pin "45") (pinfunction "PB8_45") (pintype "bidirectional"))
    )
    (net (code "77") (name "unconnected-(U4A-PB9-Pad46)") (class "Default")
      (node (ref "U4") (pin "46") (pinfunction "PB9_46") (pintype "bidirectional"))
    )
    (net (code "78") (name "unconnected-(U4A-PC13-Pad2)") (class "Default")
      (node (ref "U4") (pin "2") (pinfunction "PC13_2") (pintype "bidirectional"))
    )
    (net (code "79") (name "unconnected-(U4A-PC14-Pad3)") (class "Default")
      (node (ref "U4") (pin "3") (pinfunction "PC14_3") (pintype "bidirectional"))
    )
    (net (code "80") (name "unconnected-(U4A-PC15-Pad4)") (class "Default")
      (node (ref "U4") (pin "4") (pinfunction "PC15_4") (pintype "bidirectional"))
    )
  )
)
